# BoardConnectors.net
KiCad netlist of a schematic drawn in Altium Designer
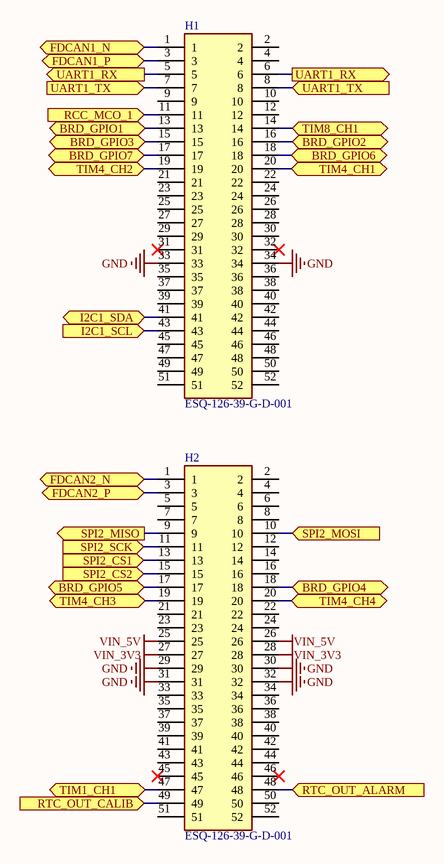
[diagram p0: BoardConnectors.SchDoc]

(export (version "E")
  (design (tool "Eeschema 10.0.6"))
  (components
    (comp (ref "H1")
      (value "ESQ-126-39-G-D-001")
      (footprint "RT_IS:RHDR52W64P254_2X26_6654X495X1135P")
      (description "52 Position Elevated Socket Connector 0.100\" (2.54mm) Through Hole Gold")
      (fields (field (name "MOUSER PART NUMBER") "200-ESQ12639GD001"))
      (libsource (lib "*") (part "ESQ-126-39-G-D-001"))
    )
    (comp (ref "H2")
      (value "ESQ-126-39-G-D-001")
      (footprint "RT_IS:RHDR52W64P254_2X26_6654X495X1135P")
      (description "52 Position Elevated Socket Connector 0.100\" (2.54mm) Through Hole Gold")
      (fields (field (name "MOUSER PART NUMBER") "200-ESQ12639GD001"))
      (libsource (lib "*") (part "ESQ-126-39-G-D-001"))
    )
  )
  (nets
    (net (code "1") (name "/BRD_GPIO1") (class "Default")
      (node (ref "H1") (pin "13") (pinfunction "13_13") (pintype "passive"))
    )
    (net (code "2") (name "/BRD_GPIO2") (class "Default")
      (node (ref "H1") (pin "16") (pinfunction "16_16") (pintype "passive"))
    )
    (net (code "3") (name "/BRD_GPIO3") (class "Default")
      (node (ref "H1") (pin "15") (pinfunction "15_15") (pintype "passive"))
    )
    (net (code "4") (name "/BRD_GPIO4") (class "Default")
      (node (ref "H2") (pin "18") (pinfunction "18_18") (pintype "passive"))
    )
    (net (code "5") (name "/BRD_GPIO5") (class "Default")
      (node (ref "H2") (pin "17") (pinfunction "17_17") (pintype "passive"))
    )
    (net (code "6") (name "/BRD_GPIO6") (class "Default")
      (node (ref "H1") (pin "18") (pinfunction "18_18") (pintype "passive"))
    )
    (net (code "7") (name "/BRD_GPIO7") (class "Default")
      (node (ref "H1") (pin "17") (pinfunction "17_17") (pintype "passive"))
    )
    (net (code "8") (name "/FDCAN1_N") (class "Default")
      (node (ref "H1") (pin "1") (pinfunction "1_1") (pintype "passive"))
    )
    (net (code "9") (name "/FDCAN1_P") (class "Default")
      (node (ref "H1") (pin "3") (pinfunction "3_3") (pintype "passive"))
    )
    (net (code "10") (name "/FDCAN2_N") (class "Default")
      (node (ref "H2") (pin "1") (pinfunction "1_1") (pintype "passive"))
    )
    (net (code "11") (name "/FDCAN2_P") (class "Default")
      (node (ref "H2") (pin "3") (pinfunction "3_3") (pintype "passive"))
    )
    (net (code "12") (name "/I2C1_SCL") (class "Default")
      (node (ref "H1") (pin "43") (pinfunction "43_43") (pintype "passive"))
    )
    (net (code "13") (name "/I2C1_SDA") (class "Default")
      (node (ref "H1") (pin "41") (pinfunction "41_41") (pintype "passive"))
    )
    (net (code "14") (name "/RCC_MCO_1") (class "Default")
      (node (ref "H1") (pin "11") (pinfunction "11_11") (pintype "passive"))
    )
    (net (code "15") (name "/RTC_OUT_ALARM") (class "Default")
      (node (ref "H2") (pin "48") (pinfunction "48_48") (pintype "passive"))
    )
    (net (code "16") (name "/RTC_OUT_CALIB") (class "Default")
      (node (ref "H2") (pin "49") (pinfunction "49_49") (pintype "passive"))
    )
    (net (code "17") (name "/SPI2_CS1") (class "Default")
      (node (ref "H2") (pin "13") (pinfunction "13_13") (pintype "passive"))
    )
    (net (code "18") (name "/SPI2_CS2") (class "Default")
      (node (ref "H2") (pin "15") (pinfunction "15_15") (pintype "passive"))
    )
    (net (code "19") (name "/SPI2_MISO") (class "Default")
      (node (ref "H2") (pin "9") (pinfunction "9_9") (pintype "passive"))
    )
    (net (code "20") (name "/SPI2_MOSI") (class "Default")
      (node (ref "H2") (pin "10") (pinfunction "10_10") (pintype "passive"))
    )
    (net (code "21") (name "/SPI2_SCK") (class "Default")
      (node (ref "H2") (pin "11") (pinfunction "11_11") (pintype "passive"))
    )
    (net (code "22") (name "/TIM1_CH1") (class "Default")
      (node (ref "H2") (pin "47") (pinfunction "47_47") (pintype "passive"))
    )
    (net (code "23") (name "/TIM4_CH1") (class "Default")
      (node (ref "H1") (pin "20") (pinfunction "20_20") (pintype "passive"))
    )
    (net (code "24") (name "/TIM4_CH2") (class "Default")
      (node (ref "H1") (pin "19") (pinfunction "19_19") (pintype "passive"))
    )
    (net (code "25") (name "/TIM4_CH3") (class "Default")
      (node (ref "H2") (pin "19") (pinfunction "19_19") (pintype "passive"))
    )
    (net (code "26") (name "/TIM4_CH4") (class "Default")
      (node (ref "H2") (pin "20") (pinfunction "20_20") (pintype "passive"))
    )
    (net (code "27") (name "/TIM8_CH1") (class "Default")
      (node (ref "H1") (pin "14") (pinfunction "14_14") (pintype "passive"))
    )
    (net (code "28") (name "/UART1_RX") (class "Default")
      (node (ref "H1") (pin "5") (pinfunction "5_5") (pintype "passive"))
      (node (ref "H1") (pin "6") (pinfunction "6_6") (pintype "passive"))
    )
    (net (code "29") (name "/UART1_TX") (class "Default")
      (node (ref "H1") (pin "7") (pinfunction "7_7") (pintype "passive"))
      (node (ref "H1") (pin "8") (pinfunction "8_8") (pintype "passive"))
    )
    (net (code "30") (name "GND") (class "Default")
      (node (ref "H1") (pin "33") (pinfunction "33_33") (pintype "passive"))
      (node (ref "H1") (pin "34") (pinfunction "34_34") (pintype "passive"))
      (node (ref "H2") (pin "29") (pinfunction "29_29") (pintype "passive"))
      (node (ref "H2") (pin "30") (pinfunction "30_30") (pintype "passive"))
      (node (ref "H2") (pin "31") (pinfunction "31_31") (pintype "passive"))
      (node (ref "H2") (pin "32") (pinfunction "32_32") (pintype "passive"))
    )
    (net (code "31") (name "VIN_3V3") (class "Default")
      (node (ref "H2") (pin "27") (pinfunction "27_27") (pintype "passive"))
      (node (ref "H2") (pin "28") (pinfunction "28_28") (pintype "passive"))
    )
    (net (code "32") (name "VIN_5V") (class "Default")
      (node (ref "H2") (pin "25") (pinfunction "25_25") (pintype "passive"))
      (node (ref "H2") (pin "26") (pinfunction "26_26") (pintype "passive"))
    )
    (net (code "33") (name "unconnected-(H1-Pad2)") (class "Default")
      (node (ref "H1") (pin "2") (pinfunction "2_2") (pintype "passive"))
    )
    (net (code "34") (name "unconnected-(H1-Pad4)") (class "Default")
      (node (ref "H1") (pin "4") (pinfunction "4_4") (pintype "passive"))
    )
    (net (code "35") (name "unconnected-(H1-Pad9)") (class "Default")
      (node (ref "H1") (pin "9") (pinfunction "9_9") (pintype "passive"))
    )
    (net (code "36") (name "unconnected-(H1-Pad10)") (class "Default")
      (node (ref "H1") (pin "10") (pinfunction "10_10") (pintype "passive"))
    )
    (net (code "37") (name "unconnected-(H1-Pad12)") (class "Default")
      (node (ref "H1") (pin "12") (pinfunction "12_12") (pintype "passive"))
    )
    (net (code "38") (name "unconnected-(H1-Pad21)") (class "Default")
      (node (ref "H1") (pin "21") (pinfunction "21_21") (pintype "passive"))
    )
    (net (code "39") (name "unconnected-(H1-Pad22)") (class "Default")
      (node (ref "H1") (pin "22") (pinfunction "22_22") (pintype "passive"))
    )
    (net (code "40") (name "unconnected-(H1-Pad23)") (class "Default")
      (node (ref "H1") (pin "23") (pinfunction "23_23") (pintype "passive"))
    )
    (net (code "41") (name "unconnected-(H1-Pad24)") (class "Default")
      (node (ref "H1") (pin "24") (pinfunction "24_24") (pintype "passive"))
    )
    (net (code "42") (name "unconnected-(H1-Pad25)") (class "Default")
      (node (ref "H1") (pin "25") (pinfunction "25_25") (pintype "passive"))
    )
    (net (code "43") (name "unconnected-(H1-Pad26)") (class "Default")
      (node (ref "H1") (pin "26") (pinfunction "26_26") (pintype "passive"))
    )
    (net (code "44") (name "unconnected-(H1-Pad27)") (class "Default")
      (node (ref "H1") (pin "27") (pinfunction "27_27") (pintype "passive"))
    )
    (net (code "45") (name "unconnected-(H1-Pad28)") (class "Default")
      (node (ref "H1") (pin "28") (pinfunction "28_28") (pintype "passive"))
    )
    (net (code "46") (name "unconnected-(H1-Pad29)") (class "Default")
      (node (ref "H1") (pin "29") (pinfunction "29_29") (pintype "passive"))
    )
    (net (code "47") (name "unconnected-(H1-Pad30)") (class "Default")
      (node (ref "H1") (pin "30") (pinfunction "30_30") (pintype "passive"))
    )
    (net (code "48") (name "unconnected-(H1-Pad31)") (class "Default")
      (node (ref "H1") (pin "31") (pinfunction "31_31") (pintype "passive+no_connect"))
    )
    (net (code "49") (name "unconnected-(H1-Pad32)") (class "Default")
      (node (ref "H1") (pin "32") (pinfunction "32_32") (pintype "passive+no_connect"))
    )
    (net (code "50") (name "unconnected-(H1-Pad35)") (class "Default")
      (node (ref "H1") (pin "35") (pinfunction "35_35") (pintype "passive"))
    )
    (net (code "51") (name "unconnected-(H1-Pad36)") (class "Default")
      (node (ref "H1") (pin "36") (pinfunction "36_36") (pintype "passive"))
    )
    (net (code "52") (name "unconnected-(H1-Pad37)") (class "Default")
      (node (ref "H1") (pin "37") (pinfunction "37_37") (pintype "passive"))
    )
    (net (code "53") (name "unconnected-(H1-Pad38)") (class "Default")
      (node (ref "H1") (pin "38") (pinfunction "38_38") (pintype "passive"))
    )
    (net (code "54") (name "unconnected-(H1-Pad39)") (class "Default")
      (node (ref "H1") (pin "39") (pinfunction "39_39") (pintype "passive"))
    )
    (net (code "55") (name "unconnected-(H1-Pad40)") (class "Default")
      (node (ref "H1") (pin "40") (pinfunction "40_40") (pintype "passive"))
    )
    (net (code "56") (name "unconnected-(H1-Pad42)") (class "Default")
      (node (ref "H1") (pin "42") (pinfunction "42_42") (pintype "passive"))
    )
    (net (code "57") (name "unconnected-(H1-Pad44)") (class "Default")
      (node (ref "H1") (pin "44") (pinfunction "44_44") (pintype "passive"))
    )
    (net (code "58") (name "unconnected-(H1-Pad45)") (class "Default")
      (node (ref "H1") (pin "45") (pinfunction "45_45") (pintype "passive"))
    )
    (net (code "59") (name "unconnected-(H1-Pad46)") (class "Default")
      (node (ref "H1") (pin "46") (pinfunction "46_46") (pintype "passive"))
    )
    (net (code "60") (name "unconnected-(H1-Pad47)") (class "Default")
      (node (ref "H1") (pin "47") (pinfunction "47_47") (pintype "passive"))
    )
    (net (code "61") (name "unconnected-(H1-Pad48)") (class "Default")
      (node (ref "H1") (pin "48") (pinfunction "48_48") (pintype "passive"))
    )
    (net (code "62") (name "unconnected-(H1-Pad49)") (class "Default")
      (node (ref "H1") (pin "49") (pinfunction "49_49") (pintype "passive"))
    )
    (net (code "63") (name "unconnected-(H1-Pad50)") (class "Default")
      (node (ref "H1") (pin "50") (pinfunction "50_50") (pintype "passive"))
    )
    (net (code "64") (name "unconnected-(H1-Pad51)") (class "Default")
      (node (ref "H1") (pin "51") (pinfunction "51_51") (pintype "passive"))
    )
    (net (code "65") (name "unconnected-(H1-Pad52)") (class "Default")
      (node (ref "H1") (pin "52") (pinfunction "52_52") (pintype "passive"))
    )
    (net (code "66") (name "unconnected-(H2-Pad2)") (class "Default")
      (node (ref "H2") (pin "2") (pinfunction "2_2") (pintype "passive"))
    )
    (net (code "67") (name "unconnected-(H2-Pad4)") (class "Default")
      (node (ref "H2") (pin "4") (pinfunction "4_4") (pintype "passive"))
    )
    (net (code "68") (name "unconnected-(H2-Pad5)") (class "Default")
      (node (ref "H2") (pin "5") (pinfunction "5_5") (pintype "passive"))
    )
    (net (code "69") (name "unconnected-(H2-Pad6)") (class "Default")
      (node (ref "H2") (pin "6") (pinfunction "6_6") (pintype "passive"))
    )
    (net (code "70") (name "unconnected-(H2-Pad7)") (class "Default")
      (node (ref "H2") (pin "7") (pinfunction "7_7") (pintype "passive"))
    )
    (net (code "71") (name "unconnected-(H2-Pad8)") (class "Default")
      (node (ref "H2") (pin "8") (pinfunction "8_8") (pintype "passive"))
    )
    (net (code "72") (name "unconnected-(H2-Pad12)") (class "Default")
      (node (ref "H2") (pin "12") (pinfunction "12_12") (pintype "passive"))
    )
    (net (code "73") (name "unconnected-(H2-Pad14)") (class "Default")
      (node (ref "H2") (pin "14") (pinfunction "14_14") (pintype "passive"))
    )
    (net (code "74") (name "unconnected-(H2-Pad16)") (class "Default")
      (node (ref "H2") (pin "16") (pinfunction "16_16") (pintype "passive"))
    )
    (net (code "75") (name "unconnected-(H2-Pad21)") (class "Default")
      (node (ref "H2") (pin "21") (pinfunction "21_21") (pintype "passive"))
    )
    (net (code "76") (name "unconnected-(H2-Pad22)") (class "Default")
      (node (ref "H2") (pin "22") (pinfunction "22_22") (pintype "passive"))
    )
    (net (code "77") (name "unconnected-(H2-Pad23)") (class "Default")
      (node (ref "H2") (pin "23") (pinfunction "23_23") (pintype "passive"))
    )
    (net (code "78") (name "unconnected-(H2-Pad24)") (class "Default")
      (node (ref "H2") (pin "24") (pinfunction "24_24") (pintype "passive"))
    )
    (net (code "79") (name "unconnected-(H2-Pad33)") (class "Default")
      (node (ref "H2") (pin "33") (pinfunction "33_33") (pintype "passive"))
    )
    (net (code "80") (name "unconnected-(H2-Pad34)") (class "Default")
      (node (ref "H2") (pin "34") (pinfunction "34_34") (pintype "passive"))
    )
    (net (code "81") (name "unconnected-(H2-Pad35)") (class "Default")
      (node (ref "H2") (pin "35") (pinfunction "35_35") (pintype "passive"))
    )
    (net (code "82") (name "unconnected-(H2-Pad36)") (class "Default")
      (node (ref "H2") (pin "36") (pinfunction "36_36") (pintype "passive"))
    )
    (net (code "83") (name "unconnected-(H2-Pad37)") (class "Default")
      (node (ref "H2") (pin "37") (pinfunction "37_37") (pintype "passive"))
    )
    (net (code "84") (name "unconnected-(H2-Pad38)") (class "Default")
      (node (ref "H2") (pin "38") (pinfunction "38_38") (pintype "passive"))
    )
    (net (code "85") (name "unconnected-(H2-Pad39)") (class "Default")
      (node (ref "H2") (pin "39") (pinfunction "39_39") (pintype "passive"))
    )
    (net (code "86") (name "unconnected-(H2-Pad40)") (class "Default")
      (node (ref "H2") (pin "40") (pinfunction "40_40") (pintype "passive"))
    )
    (net (code "87") (name "unconnected-(H2-Pad41)") (class "Default")
      (node (ref "H2") (pin "41") (pinfunction "41_41") (pintype "passive"))
    )
    (net (code "88") (name "unconnected-(H2-Pad42)") (class "Default")
      (node (ref "H2") (pin "42") (pinfunction "42_42") (pintype "passive"))
    )
    (net (code "89") (name "unconnected-(H2-Pad43)") (class "Default")
      (node (ref "H2") (pin "43") (pinfunction "43_43") (pintype "passive"))
    )
    (net (code "90") (name "unconnected-(H2-Pad44)") (class "Default")
      (node (ref "H2") (pin "44") (pinfunction "44_44") (pintype "passive"))
    )
    (net (code "91") (name "unconnected-(H2-Pad45)") (class "Default")
      (node (ref "H2") (pin "45") (pinfunction "45_45") (pintype "passive+no_connect"))
    )
    (net (code "92") (name "unconnected-(H2-Pad46)") (class "Default")
      (node (ref "H2") (pin "46") (pinfunction "46_46") (pintype "passive+no_connect"))
    )
    (net (code "93") (name "unconnected-(H2-Pad50)") (class "Default")
      (node (ref "H2") (pin "50") (pinfunction "50_50") (pintype "passive"))
    )
    (net (code "94") (name "unconnected-(H2-Pad51)") (class "Default")
      (node (ref "H2") (pin "51") (pinfunction "51_51") (pintype "passive"))
    )
    (net (code "95") (name "unconnected-(H2-Pad52)") (class "Default")
      (node (ref "H2") (pin "52") (pinfunction "52_52") (pintype "passive"))
    )
  )
)
